# PR-Modem-PY.net
KiCad netlist of a schematic drawn in EAGLE
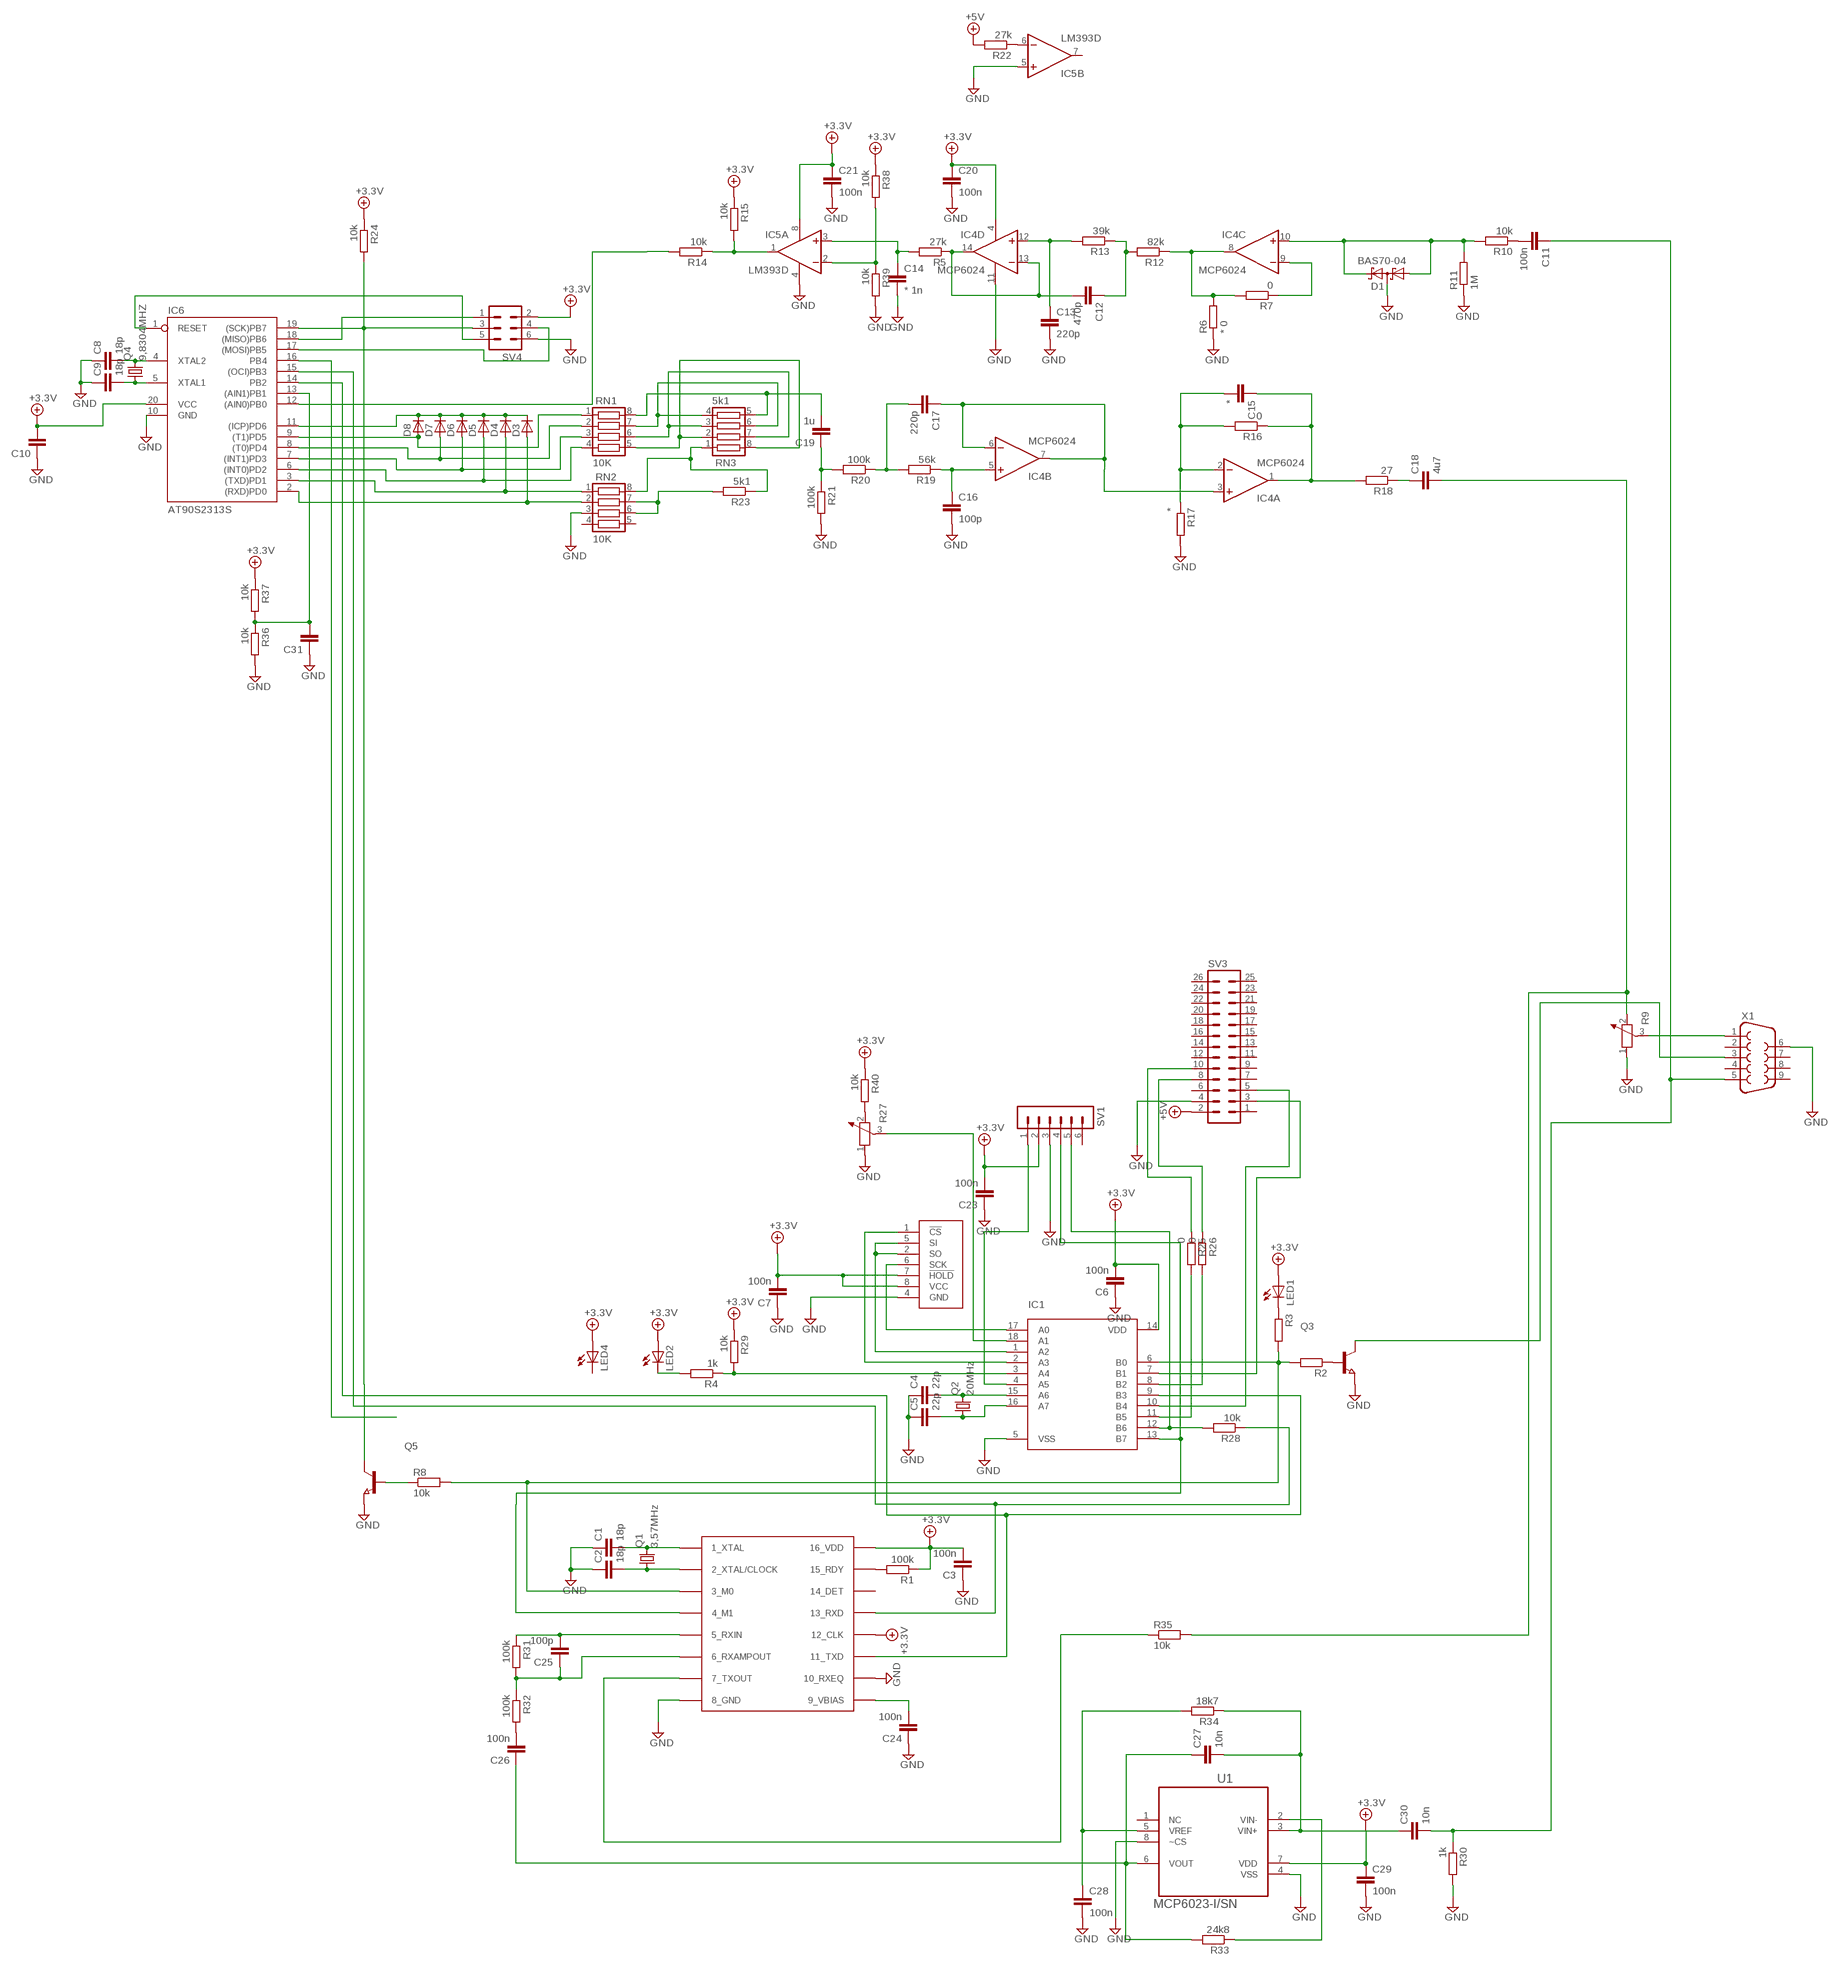
[diagram p0: schematic, sheet 1]

(export (version "E")
  (design (tool "Eeschema 10.0.6"))
  (components
    (comp (ref "C1")
      (value "18p")
      (footprint "eagle-import:C0603")
      (libsource (lib "eagle-import") (part "C-EUC0603"))
    )
    (comp (ref "C2")
      (value "18p")
      (footprint "eagle-import:C0603")
      (libsource (lib "eagle-import") (part "C-EUC0603"))
    )
    (comp (ref "C3")
      (value "100n")
      (footprint "eagle-import:C0603")
      (libsource (lib "eagle-import") (part "C-EUC0603"))
    )
    (comp (ref "C4")
      (value "22p")
      (footprint "eagle-import:C0603")
      (libsource (lib "eagle-import") (part "C-EUC0603"))
    )
    (comp (ref "C5")
      (value "22p")
      (footprint "eagle-import:C0603")
      (libsource (lib "eagle-import") (part "C-EUC0603"))
    )
    (comp (ref "C6")
      (value "100n")
      (footprint "eagle-import:C0603")
      (libsource (lib "eagle-import") (part "C-EUC0603"))
    )
    (comp (ref "C7")
      (value "100n")
      (footprint "eagle-import:C0603")
      (libsource (lib "eagle-import") (part "C-EUC0603"))
    )
    (comp (ref "C8")
      (value "18p")
      (footprint "eagle-import:C0603")
      (libsource (lib "eagle-import") (part "C-EUC0603"))
    )
    (comp (ref "C9")
      (value "18p")
      (footprint "eagle-import:C0603")
      (libsource (lib "eagle-import") (part "C-EUC0603"))
    )
    (comp (ref "C10")
      (value "C-EUC0603")
      (footprint "eagle-import:C0603")
      (libsource (lib "eagle-import") (part "C-EUC0603"))
    )
    (comp (ref "C11")
      (value "100n")
      (footprint "eagle-import:C0603")
      (libsource (lib "eagle-import") (part "C-EUC0603"))
    )
    (comp (ref "C12")
      (value "470p")
      (footprint "eagle-import:C0603")
      (libsource (lib "eagle-import") (part "C-EUC0603"))
    )
    (comp (ref "C13")
      (value "220p")
      (footprint "eagle-import:C0603")
      (libsource (lib "eagle-import") (part "C-EUC0603"))
    )
    (comp (ref "C14")
      (value "* 1n")
      (footprint "eagle-import:C0603")
      (libsource (lib "eagle-import") (part "C-EUC0603"))
    )
    (comp (ref "C15")
      (value "*")
      (footprint "eagle-import:C0603")
      (libsource (lib "eagle-import") (part "C-EUC0603"))
    )
    (comp (ref "C16")
      (value "100p")
      (footprint "eagle-import:C0603")
      (libsource (lib "eagle-import") (part "C-EUC0603"))
    )
    (comp (ref "C17")
      (value "220p")
      (footprint "eagle-import:C0603")
      (libsource (lib "eagle-import") (part "C-EUC0603"))
    )
    (comp (ref "C18")
      (value "4u7")
      (footprint "eagle-import:C1210")
      (libsource (lib "eagle-import") (part "C-EUC1210"))
    )
    (comp (ref "C19")
      (value "1u")
      (footprint "eagle-import:C1210")
      (libsource (lib "eagle-import") (part "C-EUC1210"))
    )
    (comp (ref "C20")
      (value "100n")
      (footprint "eagle-import:C0603")
      (libsource (lib "eagle-import") (part "C-EUC0603"))
    )
    (comp (ref "C21")
      (value "100n")
      (footprint "eagle-import:C0603")
      (libsource (lib "eagle-import") (part "C-EUC0603"))
    )
    (comp (ref "C23")
      (value "100n")
      (footprint "eagle-import:C0603")
      (libsource (lib "eagle-import") (part "C-EUC0603"))
    )
    (comp (ref "C24")
      (value "100n")
      (footprint "eagle-import:C0603")
      (libsource (lib "eagle-import") (part "C-EUC0603"))
    )
    (comp (ref "C25")
      (value "100p")
      (footprint "eagle-import:C0603")
      (libsource (lib "eagle-import") (part "C-EUC0603"))
    )
    (comp (ref "C26")
      (value "100n")
      (footprint "eagle-import:C0603")
      (libsource (lib "eagle-import") (part "C-EUC0603"))
    )
    (comp (ref "C27")
      (value "10n")
      (footprint "eagle-import:C0603")
      (libsource (lib "eagle-import") (part "C-EUC0603"))
    )
    (comp (ref "C28")
      (value "100n")
      (footprint "eagle-import:C0603")
      (libsource (lib "eagle-import") (part "C-EUC0603"))
    )
    (comp (ref "C29")
      (value "100n")
      (footprint "eagle-import:C0603")
      (libsource (lib "eagle-import") (part "C-EUC0603"))
    )
    (comp (ref "C30")
      (value "10n")
      (footprint "eagle-import:C0603")
      (libsource (lib "eagle-import") (part "C-EUC0603"))
    )
    (comp (ref "C31")
      (value "C-EUC0603")
      (footprint "eagle-import:C0603")
      (libsource (lib "eagle-import") (part "C-EUC0603"))
    )
    (comp (ref "D1")
      (value "BAS70-04")
      (footprint "eagle-import:SOT23")
      (libsource (lib "eagle-import") (part "BAS70-04"))
    )
    (comp (ref "D3")
      (value "D-SOD123")
      (footprint "eagle-import:SOD123")
      (libsource (lib "eagle-import") (part "D-SOD123"))
    )
    (comp (ref "D4")
      (value "D-SOD123")
      (footprint "eagle-import:SOD123")
      (libsource (lib "eagle-import") (part "D-SOD123"))
    )
    (comp (ref "D5")
      (value "D-SOD123")
      (footprint "eagle-import:SOD123")
      (libsource (lib "eagle-import") (part "D-SOD123"))
    )
    (comp (ref "D6")
      (value "D-SOD123")
      (footprint "eagle-import:SOD123")
      (libsource (lib "eagle-import") (part "D-SOD123"))
    )
    (comp (ref "D7")
      (value "D-SOD123")
      (footprint "eagle-import:SOD123")
      (libsource (lib "eagle-import") (part "D-SOD123"))
    )
    (comp (ref "D8")
      (value "D-SOD123")
      (footprint "eagle-import:SOD123")
      (libsource (lib "eagle-import") (part "D-SOD123"))
    )
    (comp (ref "IC1")
      (value "PIC16F18X7SO")
      (footprint "eagle-import:SOIC18-W")
      (libsource (lib "eagle-import") (part "PIC16F18X7SO"))
    )
    (comp (ref "IC4")
      (value "MCP6024")
      (footprint "eagle-import:SO14")
      (libsource (lib "eagle-import") (part "TL064D"))
    )
    (comp (ref "IC5")
      (value "LM393D")
      (footprint "eagle-import:SO08")
      (libsource (lib "eagle-import") (part "LM393D"))
    )
    (comp (ref "IC6")
      (value "AT90S2313S")
      (footprint "eagle-import:SO20L")
      (libsource (lib "eagle-import") (part "AT90S2313S"))
    )
    (comp (ref "LED1")
      (value "LED3MM")
      (footprint "eagle-import:LED3MM")
      (libsource (lib "eagle-import") (part "LED3MM"))
    )
    (comp (ref "LED2")
      (value "LED3MM")
      (footprint "eagle-import:LED3MM")
      (libsource (lib "eagle-import") (part "LED3MM"))
    )
    (comp (ref "LED4")
      (value "LED3MM")
      (footprint "eagle-import:LED3MM")
      (libsource (lib "eagle-import") (part "LED3MM"))
    )
    (comp (ref "Q1")
      (value "3,57MHz")
      (footprint "eagle-import:HC49_S")
      (libsource (lib "eagle-import") (part "CRYSTALHC49S"))
    )
    (comp (ref "Q2")
      (value "20MHz")
      (footprint "eagle-import:HC49_S")
      (libsource (lib "eagle-import") (part "CRYSTALHC49S"))
    )
    (comp (ref "Q3")
      (value "NPN-TRANSISTOR_SOT23")
      (footprint "eagle-import:SOT23")
      (libsource (lib "eagle-import") (part "NPN-TRANSISTOR_SOT23"))
    )
    (comp (ref "Q4")
      (value "9,8304MHZ")
      (footprint "eagle-import:HC49_S")
      (libsource (lib "eagle-import") (part "CRYSTALHC49S"))
    )
    (comp (ref "Q5")
      (value "NPN-TRANSISTOR_SOT23")
      (footprint "eagle-import:SOT23")
      (libsource (lib "eagle-import") (part "NPN-TRANSISTOR_SOT23"))
    )
    (comp (ref "R1")
      (value "100k")
      (footprint "eagle-import:R0603")
      (libsource (lib "eagle-import") (part "R-EU_R0603"))
    )
    (comp (ref "R2")
      (value "R-EU_R0603")
      (footprint "eagle-import:R0603")
      (libsource (lib "eagle-import") (part "R-EU_R0603"))
    )
    (comp (ref "R3")
      (value "R-EU_R0603")
      (footprint "eagle-import:R0603")
      (libsource (lib "eagle-import") (part "R-EU_R0603"))
    )
    (comp (ref "R4")
      (value "1k")
      (footprint "eagle-import:R0603")
      (libsource (lib "eagle-import") (part "R-EU_R0603"))
    )
    (comp (ref "R5")
      (value "27k")
      (footprint "eagle-import:R0603")
      (libsource (lib "eagle-import") (part "R-EU_R0603"))
    )
    (comp (ref "R6")
      (value "* 0")
      (footprint "eagle-import:R0603")
      (libsource (lib "eagle-import") (part "R-EU_R0603"))
    )
    (comp (ref "R7")
      (value "0")
      (footprint "eagle-import:R0603")
      (libsource (lib "eagle-import") (part "R-EU_R0603"))
    )
    (comp (ref "R8")
      (value "10k")
      (footprint "eagle-import:R0603")
      (libsource (lib "eagle-import") (part "R-EU_R0603"))
    )
    (comp (ref "R9")
      (value "POTENTIOMETER_PT-10")
      (footprint "eagle-import:PT-10")
      (libsource (lib "eagle-import") (part "POTENTIOMETER_PT-10"))
    )
    (comp (ref "R10")
      (value "10k")
      (footprint "eagle-import:R0603")
      (libsource (lib "eagle-import") (part "R-EU_R0603"))
    )
    (comp (ref "R11")
      (value "1M")
      (footprint "eagle-import:R0603")
      (libsource (lib "eagle-import") (part "R-EU_R0603"))
    )
    (comp (ref "R12")
      (value "82k")
      (footprint "eagle-import:R0603")
      (libsource (lib "eagle-import") (part "R-EU_R0603"))
    )
    (comp (ref "R13")
      (value "39k")
      (footprint "eagle-import:R0603")
      (libsource (lib "eagle-import") (part "R-EU_R0603"))
    )
    (comp (ref "R14")
      (value "10k")
      (footprint "eagle-import:R0603")
      (libsource (lib "eagle-import") (part "R-EU_R0603"))
    )
    (comp (ref "R15")
      (value "10k")
      (footprint "eagle-import:R0603")
      (libsource (lib "eagle-import") (part "R-EU_R0603"))
    )
    (comp (ref "R16")
      (value "0")
      (footprint "eagle-import:R0603")
      (libsource (lib "eagle-import") (part "R-EU_R0603"))
    )
    (comp (ref "R17")
      (value "*")
      (footprint "eagle-import:R0603")
      (libsource (lib "eagle-import") (part "R-EU_R0603"))
    )
    (comp (ref "R18")
      (value "27")
      (footprint "eagle-import:R0603")
      (libsource (lib "eagle-import") (part "R-EU_R0603"))
    )
    (comp (ref "R19")
      (value "56k")
      (footprint "eagle-import:R0603")
      (libsource (lib "eagle-import") (part "R-EU_R0603"))
    )
    (comp (ref "R20")
      (value "100k")
      (footprint "eagle-import:R0603")
      (libsource (lib "eagle-import") (part "R-EU_R0603"))
    )
    (comp (ref "R21")
      (value "100k")
      (footprint "eagle-import:R0603")
      (libsource (lib "eagle-import") (part "R-EU_R0603"))
    )
    (comp (ref "R22")
      (value "27k")
      (footprint "eagle-import:R0603")
      (libsource (lib "eagle-import") (part "R-EU_R0603"))
    )
    (comp (ref "R23")
      (value "5k1")
      (footprint "eagle-import:R0603")
      (libsource (lib "eagle-import") (part "R-EU_R0603"))
    )
    (comp (ref "R24")
      (value "10k")
      (footprint "eagle-import:R0603")
      (libsource (lib "eagle-import") (part "R-EU_R0603"))
    )
    (comp (ref "R25")
      (value "0")
      (footprint "eagle-import:R0603")
      (libsource (lib "eagle-import") (part "R-EU_R0603"))
    )
    (comp (ref "R26")
      (value "0")
      (footprint "eagle-import:R0603")
      (libsource (lib "eagle-import") (part "R-EU_R0603"))
    )
    (comp (ref "R27")
      (value "POTENTIOMETER_PT-10")
      (footprint "eagle-import:PT-10")
      (libsource (lib "eagle-import") (part "POTENTIOMETER_PT-10"))
    )
    (comp (ref "R28")
      (value "10k")
      (footprint "eagle-import:R0603")
      (libsource (lib "eagle-import") (part "R-EU_R0603"))
    )
    (comp (ref "R29")
      (value "10k")
      (footprint "eagle-import:R0603")
      (libsource (lib "eagle-import") (part "R-EU_R0603"))
    )
    (comp (ref "R30")
      (value "1k")
      (footprint "eagle-import:R0603")
      (libsource (lib "eagle-import") (part "R-EU_R0603"))
    )
    (comp (ref "R31")
      (value "100k")
      (footprint "eagle-import:R0603")
      (libsource (lib "eagle-import") (part "R-EU_R0603"))
    )
    (comp (ref "R32")
      (value "100k")
      (footprint "eagle-import:R0603")
      (libsource (lib "eagle-import") (part "R-EU_R0603"))
    )
    (comp (ref "R33")
      (value "24k8")
      (footprint "eagle-import:R0603")
      (libsource (lib "eagle-import") (part "R-EU_R0603"))
    )
    (comp (ref "R34")
      (value "18k7")
      (footprint "eagle-import:R0603")
      (libsource (lib "eagle-import") (part "R-EU_R0603"))
    )
    (comp (ref "R35")
      (value "10k")
      (footprint "eagle-import:R0603")
      (libsource (lib "eagle-import") (part "R-EU_R0603"))
    )
    (comp (ref "R36")
      (value "10k")
      (footprint "eagle-import:R0603")
      (libsource (lib "eagle-import") (part "R-EU_R0603"))
    )
    (comp (ref "R37")
      (value "10k")
      (footprint "eagle-import:R0603")
      (libsource (lib "eagle-import") (part "R-EU_R0603"))
    )
    (comp (ref "R38")
      (value "10k")
      (footprint "eagle-import:R0603")
      (libsource (lib "eagle-import") (part "R-EU_R0603"))
    )
    (comp (ref "R39")
      (value "10k")
      (footprint "eagle-import:R0603")
      (libsource (lib "eagle-import") (part "R-EU_R0603"))
    )
    (comp (ref "R40")
      (value "10k")
      (footprint "eagle-import:R0603")
      (libsource (lib "eagle-import") (part "R-EU_R0603"))
    )
    (comp (ref "RN1")
      (value "10K")
      (footprint "eagle-import:CTS742C083")
      (libsource (lib "eagle-import") (part "CTS742C083"))
    )
    (comp (ref "RN2")
      (value "10K")
      (footprint "eagle-import:CTS742C083")
      (libsource (lib "eagle-import") (part "CTS742C083"))
    )
    (comp (ref "RN3")
      (value "5k1")
      (footprint "eagle-import:CTS742C083")
      (fields (field (name "OC_FARNELL") "unknown") (field (name "OC_NEWARK") "unknown"))
      (libsource (lib "eagle-import") (part "CTS742C083"))
    )
    (comp (ref "SV1")
      (value "MA06-1")
      (footprint "eagle-import:MA06-1")
      (libsource (lib "eagle-import") (part "MA06-1"))
    )
    (comp (ref "SV3")
      (value "MA13-2")
      (footprint "eagle-import:MA13-2")
      (libsource (lib "eagle-import") (part "MA13-2"))
    )
    (comp (ref "SV4")
      (value "MA03-2")
      (footprint "eagle-import:MA03-2")
      (libsource (lib "eagle-import") (part "MA03-2"))
    )
    (comp (ref "U$1")
      (value "23K640SN")
      (footprint "eagle-import:SOIC8")
      (libsource (lib "eagle-import") (part "23K640SN"))
    )
    (comp (ref "U$2")
      (value "MX614")
      (footprint "eagle-import:SOIC16-3")
      (libsource (lib "eagle-import") (part "MX614"))
    )
    (comp (ref "U1")
      (value "MCP6023-I/SN")
      (footprint "eagle-import:SOIC127P600X175-8N")
      (libsource (lib "eagle-import") (part "MCP6023-I/SN"))
    )
    (comp (ref "X1")
      (value "F09HP")
      (footprint "eagle-import:F09HP")
      (libsource (lib "eagle-import") (part "F09HP"))
    )
  )
  (nets
    (net (code "1") (name "+3.3V") (class "Default")
      (node (ref "C10") (pin "2") (pinfunction "2_2") (pintype "passive"))
      (node (ref "C20") (pin "1") (pinfunction "1_1") (pintype "passive"))
      (node (ref "C21") (pin "1") (pinfunction "1_1") (pintype "passive"))
      (node (ref "C23") (pin "2") (pinfunction "2_2") (pintype "passive"))
      (node (ref "C29") (pin "1") (pinfunction "1_1") (pintype "passive"))
      (node (ref "C3") (pin "2") (pinfunction "2_2") (pintype "passive"))
      (node (ref "C6") (pin "2") (pinfunction "2_2") (pintype "passive"))
      (node (ref "C7") (pin "2") (pinfunction "2_2") (pintype "passive"))
      (node (ref "IC1") (pin "14") (pinfunction "VDD_14") (pintype "power_in"))
      (node (ref "IC4") (pin "4") (pinfunction "V+_4") (pintype "power_in"))
      (node (ref "IC5") (pin "8") (pinfunction "V+_8") (pintype "power_in"))
      (node (ref "IC6") (pin "20") (pinfunction "VCC_20") (pintype "power_in"))
      (node (ref "LED1") (pin "A") (pinfunction "A_A") (pintype "passive"))
      (node (ref "LED2") (pin "A") (pinfunction "A_A") (pintype "passive"))
      (node (ref "LED4") (pin "A") (pinfunction "A_A") (pintype "passive"))
      (node (ref "R1") (pin "1") (pinfunction "1_1") (pintype "passive"))
      (node (ref "R15") (pin "1") (pinfunction "1_1") (pintype "passive"))
      (node (ref "R24") (pin "1") (pinfunction "1_1") (pintype "passive"))
      (node (ref "R29") (pin "1") (pinfunction "1_1") (pintype "passive"))
      (node (ref "R37") (pin "1") (pinfunction "1_1") (pintype "passive"))
      (node (ref "R38") (pin "1") (pinfunction "1_1") (pintype "passive"))
      (node (ref "R40") (pin "1") (pinfunction "1_1") (pintype "passive"))
      (node (ref "SV1") (pin "2") (pinfunction "2_2") (pintype "passive"))
      (node (ref "SV4") (pin "2") (pinfunction "2_2") (pintype "passive"))
      (node (ref "U$1") (pin "7") (pinfunction "~{HOLD}_7") (pintype "bidirectional"))
      (node (ref "U$1") (pin "8") (pinfunction "VCC_8") (pintype "bidirectional"))
      (node (ref "U$2") (pin "12") (pinfunction "12_CLK_12") (pintype "power_in"))
      (node (ref "U$2") (pin "16") (pinfunction "16_VDD_16") (pintype "bidirectional"))
      (node (ref "U1") (pin "7") (pinfunction "VDD_7") (pintype "power_in"))
    )
    (net (code "2") (name "+5V") (class "Default")
      (node (ref "R22") (pin "2") (pinfunction "2_2") (pintype "passive"))
      (node (ref "SV3") (pin "2") (pinfunction "2_2") (pintype "passive"))
    )
    (net (code "3") (name "GND") (class "Default")
      (node (ref "C1") (pin "1") (pinfunction "1_1") (pintype "passive"))
      (node (ref "C10") (pin "1") (pinfunction "1_1") (pintype "passive"))
      (node (ref "C13") (pin "2") (pinfunction "2_2") (pintype "passive"))
      (node (ref "C14") (pin "2") (pinfunction "2_2") (pintype "passive"))
      (node (ref "C16") (pin "2") (pinfunction "2_2") (pintype "passive"))
      (node (ref "C2") (pin "1") (pinfunction "1_1") (pintype "passive"))
      (node (ref "C20") (pin "2") (pinfunction "2_2") (pintype "passive"))
      (node (ref "C21") (pin "2") (pinfunction "2_2") (pintype "passive"))
      (node (ref "C23") (pin "1") (pinfunction "1_1") (pintype "passive"))
      (node (ref "C24") (pin "1") (pinfunction "1_1") (pintype "passive"))
      (node (ref "C28") (pin "2") (pinfunction "2_2") (pintype "passive"))
      (node (ref "C29") (pin "2") (pinfunction "2_2") (pintype "passive"))
      (node (ref "C3") (pin "1") (pinfunction "1_1") (pintype "passive"))
      (node (ref "C31") (pin "1") (pinfunction "1_1") (pintype "passive"))
      (node (ref "C4") (pin "1") (pinfunction "1_1") (pintype "passive"))
      (node (ref "C5") (pin "1") (pinfunction "1_1") (pintype "passive"))
      (node (ref "C6") (pin "1") (pinfunction "1_1") (pintype "passive"))
      (node (ref "C7") (pin "1") (pinfunction "1_1") (pintype "passive"))
      (node (ref "C8") (pin "1") (pinfunction "1_1") (pintype "passive"))
      (node (ref "C9") (pin "1") (pinfunction "1_1") (pintype "passive"))
      (node (ref "D1") (pin "3") (pinfunction "C1A2_3") (pintype "passive"))
      (node (ref "IC1") (pin "5") (pinfunction "VSS_5") (pintype "power_in"))
      (node (ref "IC4") (pin "11") (pinfunction "V-_11") (pintype "power_in"))
      (node (ref "IC5") (pin "4") (pinfunction "V-_4") (pintype "power_in"))
      (node (ref "IC5") (pin "5") (pinfunction "+IN_5") (pintype "input"))
      (node (ref "IC6") (pin "10") (pinfunction "GND_10") (pintype "power_in"))
      (node (ref "Q3") (pin "2") (pinfunction "E_2") (pintype "passive"))
      (node (ref "Q5") (pin "2") (pinfunction "E_2") (pintype "passive"))
      (node (ref "R11") (pin "1") (pinfunction "1_1") (pintype "passive"))
      (node (ref "R17") (pin "2") (pinfunction "2_2") (pintype "passive"))
      (node (ref "R21") (pin "2") (pinfunction "2_2") (pintype "passive"))
      (node (ref "R27") (pin "1") (pinfunction "1_1") (pintype "passive"))
      (node (ref "R30") (pin "2") (pinfunction "2_2") (pintype "passive"))
      (node (ref "R36") (pin "2") (pinfunction "2_2") (pintype "passive"))
      (node (ref "R39") (pin "2") (pinfunction "2_2") (pintype "passive"))
      (node (ref "R6") (pin "1") (pinfunction "1_1") (pintype "passive"))
      (node (ref "R9") (pin "1") (pinfunction "1_1") (pintype "passive"))
      (node (ref "RN2") (pin "3") (pinfunction "3_3") (pintype "passive"))
      (node (ref "SV1") (pin "3") (pinfunction "3_3") (pintype "passive"))
      (node (ref "SV3") (pin "4") (pinfunction "4_4") (pintype "passive"))
      (node (ref "SV4") (pin "6") (pinfunction "6_6") (pintype "passive"))
      (node (ref "U$1") (pin "4") (pinfunction "GND_4") (pintype "bidirectional"))
      (node (ref "U$2") (pin "10") (pinfunction "10_RXEQ_10") (pintype "power_in"))
      (node (ref "U$2") (pin "8") (pinfunction "8_GND_8") (pintype "power_in"))
      (node (ref "U1") (pin "4") (pinfunction "VSS_4") (pintype "passive"))
      (node (ref "U1") (pin "8") (pinfunction "~{CS}_8") (pintype "output"))
      (node (ref "X1") (pin "6") (pinfunction "6_6") (pintype "passive"))
    )
    (net (code "4") (name "Net-(C11-Pad1)") (class "Default")
      (node (ref "C11") (pin "1") (pinfunction "1_1") (pintype "passive"))
      (node (ref "C30") (pin "2") (pinfunction "2_2") (pintype "passive"))
      (node (ref "R30") (pin "1") (pinfunction "1_1") (pintype "passive"))
      (node (ref "X1") (pin "5") (pinfunction "5_5") (pintype "passive"))
    )
    (net (code "5") (name "Net-(C11-Pad2)") (class "Default")
      (node (ref "C11") (pin "2") (pinfunction "2_2") (pintype "passive"))
      (node (ref "R10") (pin "1") (pinfunction "1_1") (pintype "passive"))
    )
    (net (code "6") (name "Net-(C12-Pad1)") (class "Default")
      (node (ref "C12") (pin "1") (pinfunction "1_1") (pintype "passive"))
      (node (ref "R12") (pin "2") (pinfunction "2_2") (pintype "passive"))
      (node (ref "R13") (pin "1") (pinfunction "1_1") (pintype "passive"))
    )
    (net (code "7") (name "Net-(C17-Pad2)") (class "Default")
      (node (ref "C17") (pin "2") (pinfunction "2_2") (pintype "passive"))
      (node (ref "R19") (pin "2") (pinfunction "2_2") (pintype "passive"))
      (node (ref "R20") (pin "1") (pinfunction "1_1") (pintype "passive"))
    )
    (net (code "8") (name "Net-(C18-Pad1)") (class "Default")
      (node (ref "C18") (pin "1") (pinfunction "1_1") (pintype "passive"))
      (node (ref "R18") (pin "1") (pinfunction "1_1") (pintype "passive"))
    )
    (net (code "9") (name "Net-(C18-Pad2)") (class "Default")
      (node (ref "C18") (pin "2") (pinfunction "2_2") (pintype "passive"))
      (node (ref "R35") (pin "2") (pinfunction "2_2") (pintype "passive"))
      (node (ref "R9") (pin "2") (pinfunction "2_2") (pintype "passive"))
    )
    (net (code "10") (name "Net-(C19-Pad1)") (class "Default")
      (node (ref "C19") (pin "1") (pinfunction "1_1") (pintype "passive"))
      (node (ref "R20") (pin "2") (pinfunction "2_2") (pintype "passive"))
      (node (ref "R21") (pin "1") (pinfunction "1_1") (pintype "passive"))
    )
    (net (code "11") (name "Net-(C19-Pad2)") (class "Default")
      (node (ref "C19") (pin "2") (pinfunction "2_2") (pintype "passive"))
      (node (ref "RN1") (pin "8") (pinfunction "8_8") (pintype "passive"))
      (node (ref "RN3") (pin "5") (pinfunction "5_5") (pintype "passive"))
    )
    (net (code "12") (name "Net-(C26-Pad2)") (class "Default")
      (node (ref "C26") (pin "2") (pinfunction "2_2") (pintype "passive"))
      (node (ref "R32") (pin "2") (pinfunction "2_2") (pintype "passive"))
    )
    (net (code "13") (name "Net-(D1-A1)") (class "Default")
      (node (ref "D1") (pin "1") (pinfunction "A1_1") (pintype "passive"))
      (node (ref "D1") (pin "2") (pinfunction "C2_2") (pintype "passive"))
      (node (ref "IC4") (pin "10") (pinfunction "+IN_10") (pintype "input"))
      (node (ref "R10") (pin "2") (pinfunction "2_2") (pintype "passive"))
      (node (ref "R11") (pin "2") (pinfunction "2_2") (pintype "passive"))
    )
    (net (code "14") (name "Net-(D3-A)") (class "Default")
      (node (ref "D3") (pin "2") (pinfunction "A_2") (pintype "passive"))
      (node (ref "IC6") (pin "2") (pinfunction "(RXD)PD0_2") (pintype "bidirectional"))
      (node (ref "RN2") (pin "2") (pinfunction "2_2") (pintype "passive"))
    )
    (net (code "15") (name "Net-(D3-C)") (class "Default")
      (node (ref "D3") (pin "1") (pinfunction "C_1") (pintype "passive"))
      (node (ref "D4") (pin "1") (pinfunction "C_1") (pintype "passive"))
      (node (ref "D5") (pin "1") (pinfunction "C_1") (pintype "passive"))
      (node (ref "D6") (pin "1") (pinfunction "C_1") (pintype "passive"))
      (node (ref "D7") (pin "1") (pinfunction "C_1") (pintype "passive"))
      (node (ref "D8") (pin "1") (pinfunction "C_1") (pintype "passive"))
      (node (ref "IC6") (pin "11") (pinfunction "(ICP)PD6_11") (pintype "bidirectional"))
    )
    (net (code "16") (name "Net-(D4-A)") (class "Default")
      (node (ref "D4") (pin "2") (pinfunction "A_2") (pintype "passive"))
      (node (ref "IC6") (pin "3") (pinfunction "(TXD)PD1_3") (pintype "bidirectional"))
      (node (ref "RN2") (pin "1") (pinfunction "1_1") (pintype "passive"))
    )
    (net (code "17") (name "Net-(D5-A)") (class "Default")
      (node (ref "D5") (pin "2") (pinfunction "A_2") (pintype "passive"))
      (node (ref "IC6") (pin "6") (pinfunction "(INT0)PD2_6") (pintype "bidirectional"))
      (node (ref "RN1") (pin "4") (pinfunction "4_4") (pintype "passive"))
    )
    (net (code "18") (name "Net-(D6-A)") (class "Default")
      (node (ref "D6") (pin "2") (pinfunction "A_2") (pintype "passive"))
      (node (ref "IC6") (pin "7") (pinfunction "(INT1)PD3_7") (pintype "bidirectional"))
      (node (ref "RN1") (pin "3") (pinfunction "3_3") (pintype "passive"))
    )
    (net (code "19") (name "Net-(D7-A)") (class "Default")
      (node (ref "D7") (pin "2") (pinfunction "A_2") (pintype "passive"))
      (node (ref "IC6") (pin "8") (pinfunction "(T0)PD4_8") (pintype "bidirectional"))
      (node (ref "RN1") (pin "2") (pinfunction "2_2") (pintype "passive"))
    )
    (net (code "20") (name "Net-(D8-A)") (class "Default")
      (node (ref "D8") (pin "2") (pinfunction "A_2") (pintype "passive"))
      (node (ref "IC6") (pin "9") (pinfunction "(T1)PD5_9") (pintype "bidirectional"))
      (node (ref "RN1") (pin "1") (pinfunction "1_1") (pintype "passive"))
    )
    (net (code "21") (name "Net-(IC1-A0)") (class "Default")
      (node (ref "IC1") (pin "17") (pinfunction "A0_17") (pintype "bidirectional"))
      (node (ref "U$1") (pin "6") (pinfunction "SCK_6") (pintype "bidirectional"))
    )
    (net (code "22") (name "Net-(IC1-A1)") (class "Default")
      (node (ref "IC1") (pin "18") (pinfunction "A1_18") (pintype "bidirectional"))
      (node (ref "R27") (pin "3") (pinfunction "3_3") (pintype "passive"))
    )
    (net (code "23") (name "Net-(IC1-A2)") (class "Default")
      (node (ref "IC1") (pin "1") (pinfunction "A2_1") (pintype "bidirectional"))
      (node (ref "U$1") (pin "2") (pinfunction "SO_2") (pintype "bidirectional"))
      (node (ref "U$1") (pin "5") (pinfunction "SI_5") (pintype "bidirectional"))
    )
    (net (code "24") (name "Net-(IC1-A3)") (class "Default")
      (node (ref "IC1") (pin "2") (pinfunction "A3_2") (pintype "bidirectional"))
      (node (ref "U$1") (pin "1") (pinfunction "~{CS}_1") (pintype "bidirectional"))
    )
    (net (code "25") (name "Net-(IC1-A4)") (class "Default")
      (node (ref "IC1") (pin "3") (pinfunction "A4_3") (pintype "bidirectional"))
      (node (ref "R29") (pin "2") (pinfunction "2_2") (pintype "passive"))
      (node (ref "R4") (pin "1") (pinfunction "1_1") (pintype "passive"))
    )
    (net (code "26") (name "Net-(IC1-A5)") (class "Default")
      (node (ref "IC1") (pin "4") (pinfunction "A5_4") (pintype "input"))
      (node (ref "SV1") (pin "1") (pinfunction "1_1") (pintype "passive"))
    )
    (net (code "27") (name "Net-(IC1-A6)") (class "Default")
      (node (ref "C4") (pin "2") (pinfunction "2_2") (pintype "passive"))
      (node (ref "IC1") (pin "15") (pinfunction "A6_15") (pintype "bidirectional"))
      (node (ref "Q2") (pin "2") (pinfunction "2_2") (pintype "passive"))
    )
    (net (code "28") (name "Net-(IC1-A7)") (class "Default")
      (node (ref "C5") (pin "2") (pinfunction "2_2") (pintype "passive"))
      (node (ref "IC1") (pin "16") (pinfunction "A7_16") (pintype "bidirectional"))
      (node (ref "Q2") (pin "1") (pinfunction "1_1") (pintype "passive"))
    )
    (net (code "29") (name "Net-(IC1-B0)") (class "Default")
      (node (ref "IC1") (pin "6") (pinfunction "B0_6") (pintype "bidirectional"))
      (node (ref "R2") (pin "2") (pinfunction "2_2") (pintype "passive"))
      (node (ref "R3") (pin "2") (pinfunction "2_2") (pintype "passive"))
      (node (ref "R8") (pin "2") (pinfunction "2_2") (pintype "passive"))
      (node (ref "U$2") (pin "3") (pinfunction "3_M0_3") (pintype "bidirectional"))
    )
    (net (code "30") (name "Net-(IC1-B1)") (class "Default")
      (node (ref "IC1") (pin "7") (pinfunction "B1_7") (pintype "bidirectional"))
      (node (ref "SV3") (pin "3") (pinfunction "3_3") (pintype "passive"))
    )
    (net (code "31") (name "Net-(IC1-B2)") (class "Default")
      (node (ref "IC1") (pin "8") (pinfunction "B2_8") (pintype "bidirectional"))
      (node (ref "R26") (pin "2") (pinfunction "2_2") (pintype "passive"))
    )
    (net (code "32") (name "Net-(IC1-B3)") (class "Default")
      (node (ref "IC1") (pin "9") (pinfunction "B3_9") (pintype "bidirectional"))
      (node (ref "IC6") (pin "14") (pinfunction "PB2_14") (pintype "bidirectional"))
      (node (ref "U$2") (pin "11") (pinfunction "11_TXD_11") (pintype "bidirectional"))
    )
    (net (code "33") (name "Net-(IC1-B4)") (class "Default")
      (node (ref "IC1") (pin "10") (pinfunction "B4_10") (pintype "bidirectional"))
      (node (ref "SV3") (pin "5") (pinfunction "5_5") (pintype "passive"))
    )
    (net (code "34") (name "Net-(IC1-B5)") (class "Default")
      (node (ref "IC1") (pin "11") (pinfunction "B5_11") (pintype "bidirectional"))
      (node (ref "R25") (pin "2") (pinfunction "2_2") (pintype "passive"))
    )
    (net (code "35") (name "Net-(IC1-B6)") (class "Default")
      (node (ref "IC1") (pin "12") (pinfunction "B6_12") (pintype "bidirectional"))
      (node (ref "R28") (pin "2") (pinfunction "2_2") (pintype "passive"))
      (node (ref "SV1") (pin "5") (pinfunction "5_5") (pintype "passive"))
    )
    (net (code "36") (name "Net-(IC1-B7)") (class "Default")
      (node (ref "IC1") (pin "13") (pinfunction "B7_13") (pintype "bidirectional"))
      (node (ref "SV1") (pin "4") (pinfunction "4_4") (pintype "passive"))
      (node (ref "U$2") (pin "4") (pinfunction "4_M1_4") (pintype "bidirectional"))
    )
    (net (code "37") (name "Net-(IC4A-+IN)") (class "Default")
      (node (ref "C17") (pin "1") (pinfunction "1_1") (pintype "passive"))
      (node (ref "IC4") (pin "3") (pinfunction "+IN_3") (pintype "input"))
      (node (ref "IC4") (pin "6") (pinfunction "-IN_6") (pintype "input"))
      (node (ref "IC4") (pin "7") (pinfunction "OUT_7") (pintype "output"))
    )
    (net (code "38") (name "Net-(IC4A--IN)") (class "Default")
      (node (ref "C15") (pin "2") (pinfunction "2_2") (pintype "passive"))
      (node (ref "IC4") (pin "2") (pinfunction "-IN_2") (pintype "input"))
      (node (ref "R16") (pin "2") (pinfunction "2_2") (pintype "passive"))
      (node (ref "R17") (pin "1") (pinfunction "1_1") (pintype "passive"))
    )
    (net (code "39") (name "Net-(IC4A-OUT)") (class "Default")
      (node (ref "C15") (pin "1") (pinfunction "1_1") (pintype "passive"))
      (node (ref "IC4") (pin "1") (pinfunction "OUT_1") (pintype "output"))
      (node (ref "R16") (pin "1") (pinfunction "1_1") (pintype "passive"))
      (node (ref "R18") (pin "2") (pinfunction "2_2") (pintype "passive"))
    )
    (net (code "40") (name "Net-(IC4B-+IN)") (class "Default")
      (node (ref "C16") (pin "1") (pinfunction "1_1") (pintype "passive"))
      (node (ref "IC4") (pin "5") (pinfunction "+IN_5") (pintype "input"))
      (node (ref "R19") (pin "1") (pinfunction "1_1") (pintype "passive"))
    )
    (net (code "41") (name "Net-(IC4C--IN)") (class "Default")
      (node (ref "IC4") (pin "9") (pinfunction "-IN_9") (pintype "input"))
      (node (ref "R7") (pin "1") (pinfunction "1_1") (pintype "passive"))
    )
    (net (code "42") (name "Net-(IC4C-OUT)") (class "Default")
      (node (ref "IC4") (pin "8") (pinfunction "OUT_8") (pintype "output"))
      (node (ref "R12") (pin "1") (pinfunction "1_1") (pintype "passive"))
      (node (ref "R6") (pin "2") (pinfunction "2_2") (pintype "passive"))
      (node (ref "R7") (pin "2") (pinfunction "2_2") (pintype "passive"))
    )
    (net (code "43") (name "Net-(IC4D-+IN)") (class "Default")
      (node (ref "C13") (pin "1") (pinfunction "1_1") (pintype "passive"))
      (node (ref "IC4") (pin "12") (pinfunction "+IN_12") (pintype "input"))
      (node (ref "R13") (pin "2") (pinfunction "2_2") (pintype "passive"))
    )
    (net (code "44") (name "Net-(IC4D--IN)") (class "Default")
      (node (ref "C12") (pin "2") (pinfunction "2_2") (pintype "passive"))
      (node (ref "IC4") (pin "13") (pinfunction "-IN_13") (pintype "input"))
      (node (ref "IC4") (pin "14") (pinfunction "OUT_14") (pintype "output"))
      (node (ref "R5") (pin "1") (pinfunction "1_1") (pintype "passive"))
    )
    (net (code "45") (name "Net-(IC5A-+IN)") (class "Default")
      (node (ref "C14") (pin "1") (pinfunction "1_1") (pintype "passive"))
      (node (ref "IC5") (pin "3") (pinfunction "+IN_3") (pintype "input"))
      (node (ref "R5") (pin "2") (pinfunction "2_2") (pintype "passive"))
    )
    (net (code "46") (name "Net-(IC5A--IN)") (class "Default")
      (node (ref "IC5") (pin "2") (pinfunction "-IN_2") (pintype "input"))
      (node (ref "R38") (pin "2") (pinfunction "2_2") (pintype "passive"))
      (node (ref "R39") (pin "1") (pinfunction "1_1") (pintype "passive"))
    )
    (net (code "47") (name "Net-(IC5A-OUT)") (class "Default")
      (node (ref "IC5") (pin "1") (pinfunction "OUT_1") (pintype "output"))
      (node (ref "R14") (pin "1") (pinfunction "1_1") (pintype "passive"))
      (node (ref "R15") (pin "2") (pinfunction "2_2") (pintype "passive"))
    )
    (net (code "48") (name "Net-(IC5B--IN)") (class "Default")
      (node (ref "IC5") (pin "6") (pinfunction "-IN_6") (pintype "input"))
      (node (ref "R22") (pin "1") (pinfunction "1_1") (pintype "passive"))
    )
    (net (code "49") (name "Net-(IC6-(AIN0)PB0)") (class "Default")
      (node (ref "IC6") (pin "12") (pinfunction "(AIN0)PB0_12") (pintype "bidirectional"))
      (node (ref "R14") (pin "2") (pinfunction "2_2") (pintype "passive"))
    )
    (net (code "50") (name "Net-(IC6-(AIN1)PB1)") (class "Default")
      (node (ref "C31") (pin "2") (pinfunction "2_2") (pintype "passive"))
      (node (ref "IC6") (pin "13") (pinfunction "(AIN1)PB1_13") (pintype "bidirectional"))
      (node (ref "R36") (pin "1") (pinfunction "1_1") (pintype "passive"))
      (node (ref "R37") (pin "2") (pinfunction "2_2") (pintype "passive"))
    )
    (net (code "51") (name "Net-(IC6-(MISO)PB6)") (class "Default")
      (node (ref "IC6") (pin "18") (pinfunction "(MISO)PB6_18") (pintype "bidirectional"))
      (node (ref "SV4") (pin "1") (pinfunction "1_1") (pintype "passive"))
    )
    (net (code "52") (name "Net-(IC6-(MOSI)PB5)") (class "Default")
      (node (ref "IC6") (pin "17") (pinfunction "(MOSI)PB5_17") (pintype "bidirectional"))
      (node (ref "SV4") (pin "4") (pinfunction "4_4") (pintype "passive"))
    )
    (net (code "53") (name "Net-(IC6-(OCI)PB3)") (class "Default")
      (node (ref "IC6") (pin "15") (pinfunction "(OCI)PB3_15") (pintype "bidirectional"))
      (node (ref "R28") (pin "1") (pinfunction "1_1") (pintype "passive"))
      (node (ref "U$2") (pin "13") (pinfunction "13_RXD_13") (pintype "bidirectional"))
    )
    (net (code "54") (name "Net-(IC6-(SCK)PB7)") (class "Default")
      (node (ref "IC6") (pin "19") (pinfunction "(SCK)PB7_19") (pintype "bidirectional"))
      (node (ref "Q5") (pin "3") (pinfunction "C_3") (pintype "passive"))
      (node (ref "R24") (pin "2") (pinfunction "2_2") (pintype "passive"))
      (node (ref "SV4") (pin "3") (pinfunction "3_3") (pintype "passive"))
    )
    (net (code "55") (name "Net-(IC6-RESET)") (class "Default")
      (node (ref "IC6") (pin "1") (pinfunction "RESET_1") (pintype "bidirectional"))
      (node (ref "SV4") (pin "5") (pinfunction "5_5") (pintype "passive"))
    )
    (net (code "56") (name "Net-(IC6-XTAL1)") (class "Default")
      (node (ref "C9") (pin "2") (pinfunction "2_2") (pintype "passive"))
      (node (ref "IC6") (pin "5") (pinfunction "XTAL1_5") (pintype "bidirectional"))
      (node (ref "Q4") (pin "1") (pinfunction "1_1") (pintype "passive"))
    )
    (net (code "57") (name "Net-(IC6-XTAL2)") (class "Default")
      (node (ref "C8") (pin "2") (pinfunction "2_2") (pintype "passive"))
      (node (ref "IC6") (pin "4") (pinfunction "XTAL2_4") (pintype "bidirectional"))
      (node (ref "Q4") (pin "2") (pinfunction "2_2") (pintype "passive"))
    )
    (net (code "58") (name "Net-(LED1-C)") (class "Default")
      (node (ref "LED1") (pin "K") (pinfunction "C_K") (pintype "passive"))
      (node (ref "R3") (pin "1") (pinfunction "1_1") (pintype "passive"))
    )
    (net (code "59") (name "Net-(LED2-C)") (class "Default")
      (node (ref "LED2") (pin "K") (pinfunction "C_K") (pintype "passive"))
      (node (ref "R4") (pin "2") (pinfunction "2_2") (pintype "passive"))
    )
    (net (code "60") (name "Net-(Q3-B)") (class "Default")
      (node (ref "Q3") (pin "1") (pinfunction "B_1") (pintype "passive"))
      (node (ref "R2") (pin "1") (pinfunction "1_1") (pintype "passive"))
    )
    (net (code "61") (name "Net-(Q3-C)") (class "Default")
      (node (ref "Q3") (pin "3") (pinfunction "C_3") (pintype "passive"))
      (node (ref "X1") (pin "3") (pinfunction "3_3") (pintype "passive"))
    )
    (net (code "62") (name "Net-(Q5-B)") (class "Default")
      (node (ref "Q5") (pin "1") (pinfunction "B_1") (pintype "passive"))
      (node (ref "R8") (pin "1") (pinfunction "1_1") (pintype "passive"))
    )
    (net (code "63") (name "Net-(R9-Pad3)") (class "Default")
      (node (ref "R9") (pin "3") (pinfunction "3_3") (pintype "passive"))
      (node (ref "X1") (pin "1") (pinfunction "1_1") (pintype "passive"))
    )
    (net (code "64") (name "Net-(R23-Pad1)") (class "Default")
      (node (ref "R23") (pin "1") (pinfunction "1_1") (pintype "passive"))
      (node (ref "RN2") (pin "8") (pinfunction "8_8") (pintype "passive"))
      (node (ref "RN3") (pin "1") (pinfunction "1_1") (pintype "passive"))
    )
    (net (code "65") (name "Net-(R23-Pad2)") (class "Default")
      (node (ref "R23") (pin "2") (pinfunction "2_2") (pintype "passive"))
      (node (ref "RN2") (pin "6") (pinfunction "6_6") (pintype "passive"))
      (node (ref "RN2") (pin "7") (pinfunction "7_7") (pintype "passive"))
    )
    (net (code "66") (name "Net-(R25-Pad1)") (class "Default")
      (node (ref "R25") (pin "1") (pinfunction "1_1") (pintype "passive"))
      (node (ref "SV3") (pin "10") (pinfunction "10_10") (pintype "passive"))
    )
    (net (code "67") (name "Net-(R26-Pad1)") (class "Default")
      (node (ref "R26") (pin "1") (pinfunction "1_1") (pintype "passive"))
      (node (ref "SV3") (pin "8") (pinfunction "8_8") (pintype "passive"))
    )
    (net (code "68") (name "Net-(R27-Pad2)") (class "Default")
      (node (ref "R27") (pin "2") (pinfunction "2_2") (pintype "passive"))
      (node (ref "R40") (pin "2") (pinfunction "2_2") (pintype "passive"))
    )
    (net (code "69") (name "Net-(RN1-Pad5)") (class "Default")
      (node (ref "RN1") (pin "5") (pinfunction "5_5") (pintype "passive"))
      (node (ref "RN3") (pin "2") (pinfunction "2_2") (pintype "passive"))
      (node (ref "RN3") (pin "8") (pinfunction "8_8") (pintype "passive"))
    )
    (net (code "70") (name "Net-(RN1-Pad6)") (class "Default")
      (node (ref "RN1") (pin "6") (pinfunction "6_6") (pintype "passive"))
      (node (ref "RN3") (pin "3") (pinfunction "3_3") (pintype "passive"))
      (node (ref "RN3") (pin "7") (pinfunction "7_7") (pintype "passive"))
    )
    (net (code "71") (name "Net-(RN1-Pad7)") (class "Default")
      (node (ref "RN1") (pin "7") (pinfunction "7_7") (pintype "passive"))
      (node (ref "RN3") (pin "4") (pinfunction "4_4") (pintype "passive"))
      (node (ref "RN3") (pin "6") (pinfunction "6_6") (pintype "passive"))
    )
    (net (code "72") (name "Net-(U$2-1_XTAL)") (class "Default")
      (node (ref "C1") (pin "2") (pinfunction "2_2") (pintype "passive"))
      (node (ref "Q1") (pin "2") (pinfunction "2_2") (pintype "passive"))
      (node (ref "U$2") (pin "1") (pinfunction "1_XTAL_1") (pintype "power_in"))
    )
    (net (code "73") (name "Net-(U$2-2_XTAL{slash}CLOCK)") (class "Default")
      (node (ref "C2") (pin "2") (pinfunction "2_2") (pintype "passive"))
      (node (ref "Q1") (pin "1") (pinfunction "1_1") (pintype "passive"))
      (node (ref "U$2") (pin "2") (pinfunction "2_XTAL/CLOCK_2") (pintype "bidirectional"))
    )
    (net (code "74") (name "Net-(U$2-5_RXIN)") (class "Default")
      (node (ref "C25") (pin "2") (pinfunction "2_2") (pintype "passive"))
      (node (ref "R31") (pin "1") (pinfunction "1_1") (pintype "passive"))
      (node (ref "U$2") (pin "5") (pinfunction "5_RXIN_5") (pintype "bidirectional"))
    )
    (net (code "75") (name "Net-(U$2-6_RXAMPOUT)") (class "Default")
      (node (ref "C25") (pin "1") (pinfunction "1_1") (pintype "passive"))
      (node (ref "R31") (pin "2") (pinfunction "2_2") (pintype "passive"))
      (node (ref "R32") (pin "1") (pinfunction "1_1") (pintype "passive"))
      (node (ref "U$2") (pin "6") (pinfunction "6_RXAMPOUT_6") (pintype "bidirectional"))
    )
    (net (code "76") (name "Net-(U$2-7_TXOUT)") (class "Default")
      (node (ref "R35") (pin "1") (pinfunction "1_1") (pintype "passive"))
      (node (ref "U$2") (pin "7") (pinfunction "7_TXOUT_7") (pintype "power_in"))
    )
    (net (code "77") (name "Net-(U$2-9_VBIAS)") (class "Default")
      (node (ref "C24") (pin "2") (pinfunction "2_2") (pintype "passive"))
      (node (ref "U$2") (pin "9") (pinfunction "9_VBIAS_9") (pintype "power_in"))
    )
    (net (code "78") (name "Net-(U$2-15_RDY)") (class "Default")
      (node (ref "R1") (pin "2") (pinfunction "2_2") (pintype "passive"))
      (node (ref "U$2") (pin "15") (pinfunction "15_RDY_15") (pintype "bidirectional"))
    )
    (net (code "79") (name "Net-(U1-VIN+)") (class "Default")
      (node (ref "C27") (pin "2") (pinfunction "2_2") (pintype "passive"))
      (node (ref "C30") (pin "1") (pinfunction "1_1") (pintype "passive"))
      (node (ref "R34") (pin "1") (pinfunction "1_1") (pintype "passive"))
      (node (ref "U1") (pin "3") (pinfunction "VIN+_3") (pintype "input"))
    )
    (net (code "80") (name "Net-(U1-VIN-)") (class "Default")
      (node (ref "R33") (pin "1") (pinfunction "1_1") (pintype "passive"))
      (node (ref "U1") (pin "2") (pinfunction "VIN-_2") (pintype "input"))
    )
    (net (code "81") (name "Net-(U1-VOUT)") (class "Default")
      (node (ref "C26") (pin "1") (pinfunction "1_1") (pintype "passive"))
      (node (ref "C27") (pin "1") (pinfunction "1_1") (pintype "passive"))
      (node (ref "R33") (pin "2") (pinfunction "2_2") (pintype "passive"))
      (node (ref "U1") (pin "6") (pinfunction "VOUT_6") (pintype "output"))
    )
    (net (code "82") (name "Net-(U1-VREF)") (class "Default")
      (node (ref "C28") (pin "1") (pinfunction "1_1") (pintype "passive"))
      (node (ref "R34") (pin "2") (pinfunction "2_2") (pintype "passive"))
      (node (ref "U1") (pin "5") (pinfunction "VREF_5") (pintype "output"))
    )
    (net (code "83") (name "unconnected-(IC5B-OUT-Pad7)") (class "Default")
      (node (ref "IC5") (pin "7") (pinfunction "OUT_7") (pintype "output"))
    )
    (net (code "84") (name "unconnected-(IC6-PB4-Pad16)") (class "Default")
      (node (ref "IC6") (pin "16") (pinfunction "PB4_16") (pintype "bidirectional"))
    )
    (net (code "85") (name "unconnected-(LED4-C-PadK)") (class "Default")
      (node (ref "LED4") (pin "K") (pinfunction "C_K") (pintype "passive"))
    )
    (net (code "86") (name "unconnected-(RN2-Pad4)") (class "Default")
      (node (ref "RN2") (pin "4") (pinfunction "4_4") (pintype "passive"))
    )
    (net (code "87") (name "unconnected-(RN2-Pad5)") (class "Default")
      (node (ref "RN2") (pin "5") (pinfunction "5_5") (pintype "passive"))
    )
    (net (code "88") (name "unconnected-(SV1-Pad6)") (class "Default")
      (node (ref "SV1") (pin "6") (pinfunction "6_6") (pintype "passive"))
    )
    (net (code "89") (name "unconnected-(SV3-Pad1)") (class "Default")
      (node (ref "SV3") (pin "1") (pinfunction "1_1") (pintype "passive"))
    )
    (net (code "90") (name "unconnected-(SV3-Pad6)") (class "Default")
      (node (ref "SV3") (pin "6") (pinfunction "6_6") (pintype "passive"))
    )
    (net (code "91") (name "unconnected-(SV3-Pad7)") (class "Default")
      (node (ref "SV3") (pin "7") (pinfunction "7_7") (pintype "passive"))
    )
    (net (code "92") (name "unconnected-(SV3-Pad9)") (class "Default")
      (node (ref "SV3") (pin "9") (pinfunction "9_9") (pintype "passive"))
    )
    (net (code "93") (name "unconnected-(SV3-Pad11)") (class "Default")
      (node (ref "SV3") (pin "11") (pinfunction "11_11") (pintype "passive"))
    )
    (net (code "94") (name "unconnected-(SV3-Pad12)") (class "Default")
      (node (ref "SV3") (pin "12") (pinfunction "12_12") (pintype "passive"))
    )
    (net (code "95") (name "unconnected-(SV3-Pad13)") (class "Default")
      (node (ref "SV3") (pin "13") (pinfunction "13_13") (pintype "passive"))
    )
    (net (code "96") (name "unconnected-(SV3-Pad14)") (class "Default")
      (node (ref "SV3") (pin "14") (pinfunction "14_14") (pintype "passive"))
    )
    (net (code "97") (name "unconnected-(SV3-Pad15)") (class "Default")
      (node (ref "SV3") (pin "15") (pinfunction "15_15") (pintype "passive"))
    )
    (net (code "98") (name "unconnected-(SV3-Pad16)") (class "Default")
      (node (ref "SV3") (pin "16") (pinfunction "16_16") (pintype "passive"))
    )
    (net (code "99") (name "unconnected-(SV3-Pad17)") (class "Default")
      (node (ref "SV3") (pin "17") (pinfunction "17_17") (pintype "passive"))
    )
    (net (code "100") (name "unconnected-(SV3-Pad18)") (class "Default")
      (node (ref "SV3") (pin "18") (pinfunction "18_18") (pintype "passive"))
    )
    (net (code "101") (name "unconnected-(SV3-Pad19)") (class "Default")
      (node (ref "SV3") (pin "19") (pinfunction "19_19") (pintype "passive"))
    )
    (net (code "102") (name "unconnected-(SV3-Pad20)") (class "Default")
      (node (ref "SV3") (pin "20") (pinfunction "20_20") (pintype "passive"))
    )
    (net (code "103") (name "unconnected-(SV3-Pad21)") (class "Default")
      (node (ref "SV3") (pin "21") (pinfunction "21_21") (pintype "passive"))
    )
    (net (code "104") (name "unconnected-(SV3-Pad22)") (class "Default")
      (node (ref "SV3") (pin "22") (pinfunction "22_22") (pintype "passive"))
    )
    (net (code "105") (name "unconnected-(SV3-Pad23)") (class "Default")
      (node (ref "SV3") (pin "23") (pinfunction "23_23") (pintype "passive"))
    )
    (net (code "106") (name "unconnected-(SV3-Pad24)") (class "Default")
      (node (ref "SV3") (pin "24") (pinfunction "24_24") (pintype "passive"))
    )
    (net (code "107") (name "unconnected-(SV3-Pad25)") (class "Default")
      (node (ref "SV3") (pin "25") (pinfunction "25_25") (pintype "passive"))
    )
    (net (code "108") (name "unconnected-(SV3-Pad26)") (class "Default")
      (node (ref "SV3") (pin "26") (pinfunction "26_26") (pintype "passive"))
    )
    (net (code "109") (name "unconnected-(U$2-14_DET-Pad14)") (class "Default")
      (node (ref "U$2") (pin "14") (pinfunction "14_DET_14") (pintype "bidirectional"))
    )
    (net (code "110") (name "unconnected-(U1-NC-Pad1)") (class "Default")
      (node (ref "U1") (pin "1") (pinfunction "NC_1") (pintype "no_connect"))
    )
    (net (code "111") (name "unconnected-(X1-Pad2)") (class "Default")
      (node (ref "X1") (pin "2") (pinfunction "2_2") (pintype "passive"))
    )
    (net (code "112") (name "unconnected-(X1-Pad4)") (class "Default")
      (node (ref "X1") (pin "4") (pinfunction "4_4") (pintype "passive"))
    )
    (net (code "113") (name "unconnected-(X1-Pad7)") (class "Default")
      (node (ref "X1") (pin "7") (pinfunction "7_7") (pintype "passive"))
    )
    (net (code "114") (name "unconnected-(X1-Pad8)") (class "Default")
      (node (ref "X1") (pin "8") (pinfunction "8_8") (pintype "passive"))
    )
    (net (code "115") (name "unconnected-(X1-Pad9)") (class "Default")
      (node (ref "X1") (pin "9") (pinfunction "9_9") (pintype "passive"))
    )
  )
)
